# ESP_CAM_VVN_v4.net
KiCad netlist of a schematic drawn in EAGLE
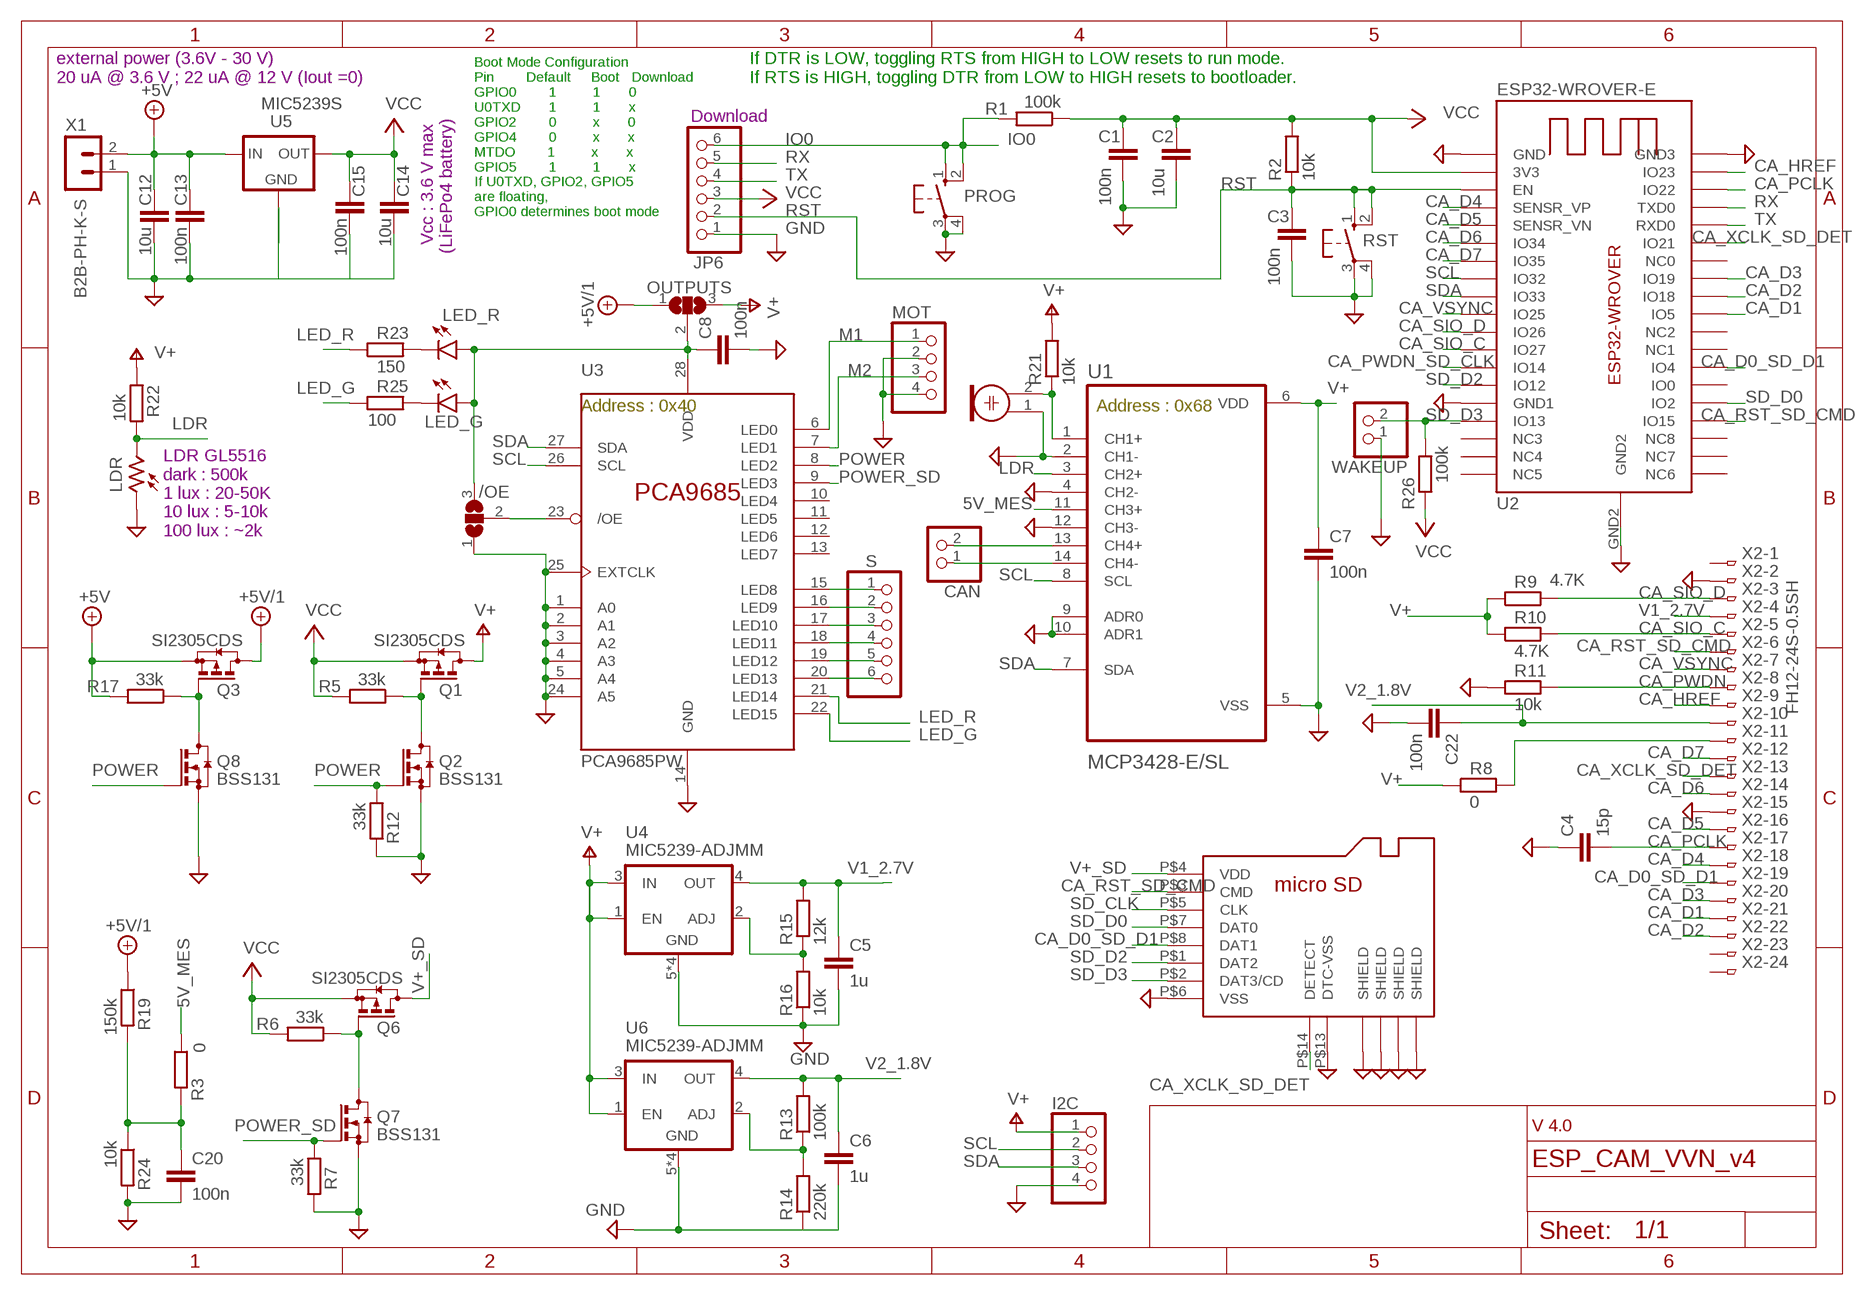
[diagram p0: schematic, sheet 1]

(export (version "E")
  (design (tool "Eeschema 10.0.6"))
  (components
    (comp (ref "/OE")
      (value "SJ2W")
      (footprint "eagle-import:SJ_2")
      (libsource (lib "eagle-import") (part "SJ2W"))
    )
    (comp (ref "C1")
      (value "100n")
      (footprint "eagle-import:C1206")
      (libsource (lib "eagle-import") (part "CC1206"))
    )
    (comp (ref "C2")
      (value "10u")
      (footprint "eagle-import:C1206")
      (libsource (lib "eagle-import") (part "CC1206"))
    )
    (comp (ref "C3")
      (value "100n")
      (footprint "eagle-import:C1206")
      (libsource (lib "eagle-import") (part "CC1206"))
    )
    (comp (ref "C4")
      (value "15p")
      (footprint "eagle-import:C1206")
      (libsource (lib "eagle-import") (part "CC1206"))
    )
    (comp (ref "C5")
      (value "1u")
      (footprint "eagle-import:C1206")
      (libsource (lib "eagle-import") (part "C-EUC1206"))
    )
    (comp (ref "C6")
      (value "1u")
      (footprint "eagle-import:C1206")
      (libsource (lib "eagle-import") (part "C-EUC1206"))
    )
    (comp (ref "C7")
      (value "100n")
      (footprint "eagle-import:C1206")
      (libsource (lib "eagle-import") (part "CC1206"))
    )
    (comp (ref "C8")
      (value "100n")
      (footprint "eagle-import:C1206")
      (libsource (lib "eagle-import") (part "CC1206"))
    )
    (comp (ref "C12")
      (value "10u")
      (footprint "eagle-import:C1206")
      (libsource (lib "eagle-import") (part "CC1206"))
    )
    (comp (ref "C13")
      (value "100n")
      (footprint "eagle-import:C1206")
      (libsource (lib "eagle-import") (part "CC1206"))
    )
    (comp (ref "C14")
      (value "10u")
      (footprint "eagle-import:C1206")
      (libsource (lib "eagle-import") (part "CC1206"))
    )
    (comp (ref "C15")
      (value "100n")
      (footprint "eagle-import:C1206")
      (libsource (lib "eagle-import") (part "CC1206"))
    )
    (comp (ref "C20")
      (value "100n")
      (footprint "eagle-import:C1206")
      (libsource (lib "eagle-import") (part "CC1206"))
    )
    (comp (ref "C22")
      (value "100n")
      (footprint "eagle-import:C1206")
      (libsource (lib "eagle-import") (part "CC1206"))
    )
    (comp (ref "CAN")
      (value "PINHD-1X2")
      (footprint "eagle-import:1X02")
      (libsource (lib "eagle-import") (part "PINHD-1X2"))
    )
    (comp (ref "I2C")
      (value "PINHD-1X4")
      (footprint "eagle-import:1X04")
      (libsource (lib "eagle-import") (part "PINHD-1X4"))
    )
    (comp (ref "JP6")
      (value "PINHD-1X6/90")
      (footprint "eagle-import:1X06_90")
      (libsource (lib "eagle-import") (part "PINHD-1X6/90"))
    )
    (comp (ref "LDR")
      (value "VT93N2")
      (footprint "eagle-import:VT900")
      (libsource (lib "eagle-import") (part "VT93N2"))
    )
    (comp (ref "LED_G")
      (value "LEDSMT1206")
      (footprint "eagle-import:1206")
      (libsource (lib "eagle-import") (part "LEDSMT1206"))
    )
    (comp (ref "LED_R")
      (value "LEDSMT1206")
      (footprint "eagle-import:1206")
      (libsource (lib "eagle-import") (part "LEDSMT1206"))
    )
    (comp (ref "M1")
      (value "ELECTRET_MICROPHON-WM-62PC/62PK")
      (footprint "eagle-import:WM-62PC_62PK")
      (libsource (lib "eagle-import") (part "ELECTRET_MICROPHON-WM-62PC/62PK"))
    )
    (comp (ref "MOT")
      (value "PINHD-1X4")
      (footprint "eagle-import:1X04")
      (libsource (lib "eagle-import") (part "PINHD-1X4"))
    )
    (comp (ref "OUTPUTS")
      (value "SJ2W")
      (footprint "eagle-import:SJ_2")
      (libsource (lib "eagle-import") (part "SJ2W"))
    )
    (comp (ref "PROG")
      (value "10-XX")
      (footprint "eagle-import:B3F-10XX")
      (fields (field (name "MPN") "B3F-1000"))
      (libsource (lib "eagle-import") (part "10-XX"))
    )
    (comp (ref "Q1")
      (value "SI2305CDS")
      (footprint "eagle-import:SOT23")
      (libsource (lib "eagle-import") (part "SI2305CDS"))
    )
    (comp (ref "Q2")
      (value "BSS131")
      (footprint "eagle-import:SOT23")
      (libsource (lib "eagle-import") (part "BSS131"))
    )
    (comp (ref "Q3")
      (value "SI2305CDS")
      (footprint "eagle-import:SOT23")
      (libsource (lib "eagle-import") (part "SI2305CDS"))
    )
    (comp (ref "Q6")
      (value "SI2305CDS")
      (footprint "eagle-import:SOT23")
      (libsource (lib "eagle-import") (part "SI2305CDS"))
    )
    (comp (ref "Q7")
      (value "BSS131")
      (footprint "eagle-import:SOT23")
      (libsource (lib "eagle-import") (part "BSS131"))
    )
    (comp (ref "Q8")
      (value "BSS131")
      (footprint "eagle-import:SOT23")
      (libsource (lib "eagle-import") (part "BSS131"))
    )
    (comp (ref "R1")
      (value "100k")
      (footprint "eagle-import:R1206")
      (libsource (lib "eagle-import") (part "RR1206"))
    )
    (comp (ref "R2")
      (value "10k")
      (footprint "eagle-import:R1206")
      (libsource (lib "eagle-import") (part "RR1206"))
    )
    (comp (ref "R3")
      (value "0")
      (footprint "eagle-import:R1206")
      (libsource (lib "eagle-import") (part "RR1206"))
    )
    (comp (ref "R5")
      (value "33k")
      (footprint "eagle-import:R1206")
      (libsource (lib "eagle-import") (part "RR1206"))
    )
    (comp (ref "R6")
      (value "33k")
      (footprint "eagle-import:R1206")
      (libsource (lib "eagle-import") (part "RR1206"))
    )
    (comp (ref "R7")
      (value "33k")
      (footprint "eagle-import:R1206")
      (libsource (lib "eagle-import") (part "RR1206"))
    )
    (comp (ref "R8")
      (value "0")
      (footprint "eagle-import:R1206")
      (libsource (lib "eagle-import") (part "RR1206"))
    )
    (comp (ref "R9")
      (value "4.7K")
      (footprint "eagle-import:R1206")
      (libsource (lib "eagle-import") (part "RR1206"))
    )
    (comp (ref "R10")
      (value "4.7K")
      (footprint "eagle-import:R1206")
      (libsource (lib "eagle-import") (part "RR1206"))
    )
    (comp (ref "R11")
      (value "10k")
      (footprint "eagle-import:R1206")
      (libsource (lib "eagle-import") (part "RR1206"))
    )
    (comp (ref "R12")
      (value "33k")
      (footprint "eagle-import:R1206")
      (libsource (lib "eagle-import") (part "RR1206"))
    )
    (comp (ref "R13")
      (value "100k")
      (footprint "eagle-import:R1206")
      (libsource (lib "eagle-import") (part "R-EU_R1206"))
    )
    (comp (ref "R14")
      (value "220k")
      (footprint "eagle-import:R1206")
      (libsource (lib "eagle-import") (part "R-EU_R1206"))
    )
    (comp (ref "R15")
      (value "12k")
      (footprint "eagle-import:R1206")
      (libsource (lib "eagle-import") (part "R-EU_R1206"))
    )
    (comp (ref "R16")
      (value "10k")
      (footprint "eagle-import:R1206")
      (libsource (lib "eagle-import") (part "R-EU_R1206"))
    )
    (comp (ref "R17")
      (value "33k")
      (footprint "eagle-import:R1206")
      (libsource (lib "eagle-import") (part "RR1206"))
    )
    (comp (ref "R19")
      (value "150k")
      (footprint "eagle-import:R1206")
      (libsource (lib "eagle-import") (part "RR1206"))
    )
    (comp (ref "R21")
      (value "10k")
      (footprint "eagle-import:R1206")
      (libsource (lib "eagle-import") (part "RR1206"))
    )
    (comp (ref "R22")
      (value "10k")
      (footprint "eagle-import:R1206")
      (libsource (lib "eagle-import") (part "RR1206"))
    )
    (comp (ref "R23")
      (value "150")
      (footprint "eagle-import:R1206")
      (libsource (lib "eagle-import") (part "RR1206"))
    )
    (comp (ref "R24")
      (value "10k")
      (footprint "eagle-import:R1206")
      (libsource (lib "eagle-import") (part "RR1206"))
    )
    (comp (ref "R25")
      (value "100")
      (footprint "eagle-import:R1206")
      (libsource (lib "eagle-import") (part "RR1206"))
    )
    (comp (ref "R26")
      (value "100k")
      (footprint "eagle-import:R1206")
      (libsource (lib "eagle-import") (part "RR1206"))
    )
    (comp (ref "RST")
      (value "10-XX")
      (footprint "eagle-import:B3F-10XX")
      (fields (field (name "MPN") "B3F-1000"))
      (libsource (lib "eagle-import") (part "10-XX"))
    )
    (comp (ref "S")
      (value "PINHD-1X6")
      (footprint "eagle-import:1X06")
      (libsource (lib "eagle-import") (part "PINHD-1X6"))
    )
    (comp (ref "SD1")
      (value "MICRO-SD-8")
      (footprint "eagle-import:MICROSDMOLEX")
      (libsource (lib "eagle-import") (part "MICRO-SD-8"))
    )
    (comp (ref "U1")
      (value "MCP3428-E/SL")
      (footprint "eagle-import:SOIC127P600X175-14N")
      (fields (field (name "MF") "Microchip"))
      (libsource (lib "eagle-import") (part "MCP3428-E/SL"))
    )
    (comp (ref "U2")
      (value "ESP32-WROVER-E")
      (footprint "eagle-import:ESP32-WROVER")
      (libsource (lib "eagle-import") (part "ESP32-WROVER-E"))
    )
    (comp (ref "U3")
      (value "PCA9685PW")
      (footprint "eagle-import:TSSOP28")
      (libsource (lib "eagle-import") (part "PCA9685PW"))
    )
    (comp (ref "U4")
      (value "MIC5239-ADJMM")
      (footprint "eagle-import:MSOP08")
      (libsource (lib "eagle-import") (part "MIC5239-ADJMM"))
    )
    (comp (ref "U5")
      (value "MIC5239S")
      (footprint "eagle-import:SOT223")
      (libsource (lib "eagle-import") (part "MIC5239S"))
    )
    (comp (ref "U6")
      (value "MIC5239-ADJMM")
      (footprint "eagle-import:MSOP08")
      (libsource (lib "eagle-import") (part "MIC5239-ADJMM"))
    )
    (comp (ref "WAKEUP")
      (value "PINHD-1X2")
      (footprint "eagle-import:1X02")
      (libsource (lib "eagle-import") (part "PINHD-1X2"))
    )
    (comp (ref "X1")
      (value "B2B-PH-K-S")
      (footprint "eagle-import:B2B-PH-K-S")
      (libsource (lib "eagle-import") (part "B2B-PH-K-S"))
    )
    (comp (ref "X2")
      (value "FH12-24S-0.5SH")
      (footprint "eagle-import:FH12-24S-0.5SH")
      (fields (field (name "MPN") "FH12-24S-0.5SH(55)"))
      (libsource (lib "eagle-import") (part "FH12-24S-0.5SH"))
    )
  )
  (nets
    (net (code "1") (name "+5V") (class "Default")
      (node (ref "C12") (pin "1") (pinfunction "1_1") (pintype "passive"))
      (node (ref "C13") (pin "1") (pinfunction "1_1") (pintype "passive"))
      (node (ref "Q3") (pin "2") (pinfunction "S_2") (pintype "passive"))
      (node (ref "R17") (pin "2") (pinfunction "2_2") (pintype "passive"))
      (node (ref "U5") (pin "1") (pinfunction "IN_1") (pintype "input"))
      (node (ref "X1") (pin "2") (pinfunction "2_2") (pintype "passive"))
    )
    (net (code "2") (name "+5V{slash}1") (class "Default")
      (node (ref "OUTPUTS") (pin "1") (pinfunction "1_1") (pintype "passive"))
      (node (ref "Q3") (pin "3") (pinfunction "D_3") (pintype "passive"))
      (node (ref "R19") (pin "1") (pinfunction "1_1") (pintype "passive"))
    )
    (net (code "3") (name "/5V_MES") (class "Default")
      (node (ref "R3") (pin "1") (pinfunction "1_1") (pintype "passive"))
      (node (ref "U1") (pin "11") (pinfunction "CH3+_11") (pintype "input"))
    )
    (net (code "4") (name "/CA_D0_SD_D1") (class "Default")
      (node (ref "SD1") (pin "P$8") (pinfunction "DAT1_P$8") (pintype "bidirectional"))
      (node (ref "U2") (pin "IO4") (pinfunction "IO4_IO4") (pintype "bidirectional"))
      (node (ref "X2") (pin "19") (pinfunction "1_19") (pintype "passive"))
    )
    (net (code "5") (name "/CA_D1") (class "Default")
      (node (ref "U2") (pin "IO5") (pinfunction "IO5_IO5") (pintype "bidirectional"))
      (node (ref "X2") (pin "21") (pinfunction "1_21") (pintype "passive"))
    )
    (net (code "6") (name "/CA_D2") (class "Default")
      (node (ref "U2") (pin "IO18") (pinfunction "IO18_IO18") (pintype "bidirectional"))
      (node (ref "X2") (pin "22") (pinfunction "1_22") (pintype "passive"))
    )
    (net (code "7") (name "/CA_D3") (class "Default")
      (node (ref "U2") (pin "IO19") (pinfunction "IO19_IO19") (pintype "bidirectional"))
      (node (ref "X2") (pin "20") (pinfunction "1_20") (pintype "passive"))
    )
    (net (code "8") (name "/CA_D4") (class "Default")
      (node (ref "U2") (pin "SENSOR_VP") (pinfunction "SENSR_VP_SENSOR_VP") (pintype "bidirectional"))
      (node (ref "X2") (pin "18") (pinfunction "1_18") (pintype "passive"))
    )
    (net (code "9") (name "/CA_D5") (class "Default")
      (node (ref "U2") (pin "SENSOR_VN") (pinfunction "SENSR_VN_SENSOR_VN") (pintype "bidirectional"))
      (node (ref "X2") (pin "16") (pinfunction "1_16") (pintype "passive"))
    )
    (net (code "10") (name "/CA_D6") (class "Default")
      (node (ref "U2") (pin "IO34") (pinfunction "IO34_IO34") (pintype "bidirectional"))
      (node (ref "X2") (pin "14") (pinfunction "1_14") (pintype "passive"))
    )
    (net (code "11") (name "/CA_D7") (class "Default")
      (node (ref "U2") (pin "IO35") (pinfunction "IO35_IO35") (pintype "bidirectional"))
      (node (ref "X2") (pin "12") (pinfunction "1_12") (pintype "passive"))
    )
    (net (code "12") (name "/CA_HREF") (class "Default")
      (node (ref "U2") (pin "IO23") (pinfunction "IO23_IO23") (pintype "bidirectional"))
      (node (ref "X2") (pin "9") (pinfunction "1_9") (pintype "passive"))
    )
    (net (code "13") (name "/CA_PCLK") (class "Default")
      (node (ref "C4") (pin "2") (pinfunction "2_2") (pintype "passive"))
      (node (ref "U2") (pin "IO22") (pinfunction "IO22_IO22") (pintype "bidirectional"))
      (node (ref "X2") (pin "17") (pinfunction "1_17") (pintype "passive"))
    )
    (net (code "14") (name "/CA_PWDN") (class "Default")
      (node (ref "R11") (pin "2") (pinfunction "2_2") (pintype "passive"))
      (node (ref "X2") (pin "8") (pinfunction "1_8") (pintype "passive"))
    )
    (net (code "15") (name "/CA_PWDN_SD_CLK") (class "Default")
      (node (ref "U2") (pin "IO14") (pinfunction "IO14_IO14") (pintype "bidirectional"))
    )
    (net (code "16") (name "/CA_RST_SD_CMD") (class "Default")
      (node (ref "SD1") (pin "P$3") (pinfunction "CMD_P$3") (pintype "bidirectional"))
      (node (ref "U2") (pin "IO15") (pinfunction "IO15_IO15") (pintype "bidirectional"))
      (node (ref "X2") (pin "6") (pinfunction "1_6") (pintype "passive"))
    )
    (net (code "17") (name "/CA_SIO_C") (class "Default")
      (node (ref "R10") (pin "2") (pinfunction "2_2") (pintype "passive"))
      (node (ref "U2") (pin "IO27") (pinfunction "IO27_IO27") (pintype "bidirectional"))
      (node (ref "X2") (pin "5") (pinfunction "1_5") (pintype "passive"))
    )
    (net (code "18") (name "/CA_SIO_D") (class "Default")
      (node (ref "R9") (pin "2") (pinfunction "2_2") (pintype "passive"))
      (node (ref "U2") (pin "IO26") (pinfunction "IO26_IO26") (pintype "bidirectional"))
      (node (ref "X2") (pin "3") (pinfunction "1_3") (pintype "passive"))
    )
    (net (code "19") (name "/CA_VSYNC") (class "Default")
      (node (ref "U2") (pin "IO25") (pinfunction "IO25_IO25") (pintype "bidirectional"))
      (node (ref "X2") (pin "7") (pinfunction "1_7") (pintype "passive"))
    )
    (net (code "20") (name "/CA_XCLK_SD_DET") (class "Default")
      (node (ref "SD1") (pin "P$14") (pinfunction "DETECT_P$14") (pintype "power_in"))
      (node (ref "U2") (pin "IO21") (pinfunction "IO21_IO21") (pintype "bidirectional"))
      (node (ref "X2") (pin "13") (pinfunction "1_13") (pintype "passive"))
    )
    (net (code "21") (name "/IO0") (class "Default")
      (node (ref "JP6") (pin "6") (pinfunction "6_6") (pintype "passive"))
      (node (ref "PROG") (pin "1") (pinfunction "S_1") (pintype "passive"))
      (node (ref "PROG") (pin "2") (pinfunction "S1_2") (pintype "passive"))
      (node (ref "R1") (pin "2") (pinfunction "2_2") (pintype "passive"))
    )
    (net (code "22") (name "/LDR") (class "Default")
      (node (ref "LDR") (pin "2") (pinfunction "2_2") (pintype "passive"))
      (node (ref "R22") (pin "2") (pinfunction "2_2") (pintype "passive"))
      (node (ref "U1") (pin "3") (pinfunction "CH2+_3") (pintype "input"))
    )
    (net (code "23") (name "/LED_G") (class "Default")
      (node (ref "R25") (pin "1") (pinfunction "1_1") (pintype "passive"))
      (node (ref "U3") (pin "22") (pinfunction "LED15_22") (pintype "bidirectional"))
    )
    (net (code "24") (name "/LED_R") (class "Default")
      (node (ref "R23") (pin "1") (pinfunction "1_1") (pintype "passive"))
      (node (ref "U3") (pin "21") (pinfunction "LED14_21") (pintype "bidirectional"))
    )
    (net (code "25") (name "/M1") (class "Default")
      (node (ref "MOT") (pin "1") (pinfunction "1_1") (pintype "passive"))
      (node (ref "U3") (pin "6") (pinfunction "LED0_6") (pintype "bidirectional"))
    )
    (net (code "26") (name "/M2") (class "Default")
      (node (ref "MOT") (pin "3") (pinfunction "3_3") (pintype "passive"))
      (node (ref "U3") (pin "7") (pinfunction "LED1_7") (pintype "bidirectional"))
    )
    (net (code "27") (name "/POWER") (class "Default")
      (node (ref "Q2") (pin "1") (pinfunction "G_1") (pintype "passive"))
      (node (ref "Q8") (pin "1") (pinfunction "G_1") (pintype "passive"))
      (node (ref "R12") (pin "1") (pinfunction "1_1") (pintype "passive"))
      (node (ref "U3") (pin "8") (pinfunction "LED2_8") (pintype "bidirectional"))
    )
    (net (code "28") (name "/POWER_SD") (class "Default")
      (node (ref "Q7") (pin "1") (pinfunction "G_1") (pintype "passive"))
      (node (ref "R7") (pin "1") (pinfunction "1_1") (pintype "passive"))
      (node (ref "U3") (pin "9") (pinfunction "LED3_9") (pintype "bidirectional"))
    )
    (net (code "29") (name "/RST") (class "Default")
      (node (ref "C3") (pin "1") (pinfunction "1_1") (pintype "passive"))
      (node (ref "JP6") (pin "2") (pinfunction "2_2") (pintype "passive"))
      (node (ref "R2") (pin "1") (pinfunction "1_1") (pintype "passive"))
      (node (ref "RST") (pin "1") (pinfunction "S_1") (pintype "passive"))
      (node (ref "RST") (pin "2") (pinfunction "S1_2") (pintype "passive"))
      (node (ref "U2") (pin "EN") (pinfunction "EN_EN") (pintype "bidirectional"))
    )
    (net (code "30") (name "/RX") (class "Default")
      (node (ref "JP6") (pin "5") (pinfunction "5_5") (pintype "passive"))
      (node (ref "U2") (pin "TXD0") (pinfunction "TXD0_TXD0") (pintype "bidirectional"))
    )
    (net (code "31") (name "/SCL") (class "Default")
      (node (ref "I2C") (pin "2") (pinfunction "2_2") (pintype "passive"))
      (node (ref "U1") (pin "8") (pinfunction "SCL_8") (pintype "input"))
      (node (ref "U2") (pin "IO32") (pinfunction "IO32_IO32") (pintype "bidirectional"))
      (node (ref "U3") (pin "26") (pinfunction "SCL_26") (pintype "bidirectional"))
    )
    (net (code "32") (name "/SDA") (class "Default")
      (node (ref "I2C") (pin "3") (pinfunction "3_3") (pintype "passive"))
      (node (ref "U1") (pin "7") (pinfunction "SDA_7") (pintype "bidirectional"))
      (node (ref "U2") (pin "IO33") (pinfunction "IO33_IO33") (pintype "bidirectional"))
      (node (ref "U3") (pin "27") (pinfunction "SDA_27") (pintype "bidirectional"))
    )
    (net (code "33") (name "/SD_CLK") (class "Default")
      (node (ref "SD1") (pin "P$5") (pinfunction "CLK_P$5") (pintype "bidirectional"))
    )
    (net (code "34") (name "/SD_D0") (class "Default")
      (node (ref "SD1") (pin "P$7") (pinfunction "DAT0_P$7") (pintype "bidirectional"))
      (node (ref "U2") (pin "IO2") (pinfunction "IO2_IO2") (pintype "bidirectional"))
    )
    (net (code "35") (name "/SD_D2") (class "Default")
      (node (ref "SD1") (pin "P$1") (pinfunction "DAT2_P$1") (pintype "bidirectional"))
      (node (ref "U2") (pin "IO12") (pinfunction "IO12_IO12") (pintype "bidirectional"))
    )
    (net (code "36") (name "/SD_D3") (class "Default")
      (node (ref "R26") (pin "2") (pinfunction "2_2") (pintype "passive"))
      (node (ref "SD1") (pin "P$2") (pinfunction "DAT3/CD_P$2") (pintype "bidirectional"))
      (node (ref "U2") (pin "IO13") (pinfunction "IO13_IO13") (pintype "bidirectional"))
      (node (ref "WAKEUP") (pin "2") (pinfunction "2_2") (pintype "passive"))
    )
    (net (code "37") (name "/TX") (class "Default")
      (node (ref "JP6") (pin "4") (pinfunction "4_4") (pintype "passive"))
      (node (ref "U2") (pin "RXD0") (pinfunction "RXD0_RXD0") (pintype "bidirectional"))
    )
    (net (code "38") (name "/V+_SD") (class "Default")
      (node (ref "Q6") (pin "3") (pinfunction "D_3") (pintype "passive"))
      (node (ref "SD1") (pin "P$4") (pinfunction "VDD_P$4") (pintype "power_in"))
    )
    (net (code "39") (name "/V1_2.7V") (class "Default")
      (node (ref "C5") (pin "1") (pinfunction "1_1") (pintype "passive"))
      (node (ref "R15") (pin "2") (pinfunction "2_2") (pintype "passive"))
      (node (ref "U4") (pin "4") (pinfunction "OUT_4") (pintype "passive"))
      (node (ref "X2") (pin "4") (pinfunction "1_4") (pintype "passive"))
    )
    (net (code "40") (name "/V2_1.8V") (class "Default")
      (node (ref "C22") (pin "1") (pinfunction "1_1") (pintype "passive"))
      (node (ref "C6") (pin "1") (pinfunction "1_1") (pintype "passive"))
      (node (ref "R13") (pin "2") (pinfunction "2_2") (pintype "passive"))
      (node (ref "U6") (pin "4") (pinfunction "OUT_4") (pintype "passive"))
      (node (ref "X2") (pin "10") (pinfunction "1_10") (pintype "passive"))
    )
    (net (code "41") (name "GND") (class "Default")
      (node (ref "/OE") (pin "1") (pinfunction "1_1") (pintype "passive"))
      (node (ref "C1") (pin "2") (pinfunction "2_2") (pintype "passive"))
      (node (ref "C12") (pin "2") (pinfunction "2_2") (pintype "passive"))
      (node (ref "C13") (pin "2") (pinfunction "2_2") (pintype "passive"))
      (node (ref "C14") (pin "2") (pinfunction "2_2") (pintype "passive"))
      (node (ref "C15") (pin "2") (pinfunction "2_2") (pintype "passive"))
      (node (ref "C2") (pin "2") (pinfunction "2_2") (pintype "passive"))
      (node (ref "C20") (pin "2") (pinfunction "2_2") (pintype "passive"))
      (node (ref "C22") (pin "2") (pinfunction "2_2") (pintype "passive"))
      (node (ref "C3") (pin "2") (pinfunction "2_2") (pintype "passive"))
      (node (ref "C4") (pin "1") (pinfunction "1_1") (pintype "passive"))
      (node (ref "C5") (pin "2") (pinfunction "2_2") (pintype "passive"))
      (node (ref "C6") (pin "2") (pinfunction "2_2") (pintype "passive"))
      (node (ref "C7") (pin "2") (pinfunction "2_2") (pintype "passive"))
      (node (ref "C8") (pin "2") (pinfunction "2_2") (pintype "passive"))
      (node (ref "I2C") (pin "4") (pinfunction "4_4") (pintype "passive"))
      (node (ref "JP6") (pin "1") (pinfunction "1_1") (pintype "passive"))
      (node (ref "LDR") (pin "1") (pinfunction "1_1") (pintype "passive"))
      (node (ref "M1") (pin "1") (pinfunction "1_1") (pintype "passive"))
      (node (ref "MOT") (pin "2") (pinfunction "2_2") (pintype "passive"))
      (node (ref "MOT") (pin "4") (pinfunction "4_4") (pintype "passive"))
      (node (ref "PROG") (pin "3") (pinfunction "P_3") (pintype "passive"))
      (node (ref "PROG") (pin "4") (pinfunction "P1_4") (pintype "passive"))
      (node (ref "Q2") (pin "2") (pinfunction "S_2") (pintype "passive"))
      (node (ref "Q7") (pin "2") (pinfunction "S_2") (pintype "passive"))
      (node (ref "Q8") (pin "2") (pinfunction "S_2") (pintype "passive"))
      (node (ref "R11") (pin "1") (pinfunction "1_1") (pintype "passive"))
      (node (ref "R12") (pin "2") (pinfunction "2_2") (pintype "passive"))
      (node (ref "R14") (pin "1") (pinfunction "1_1") (pintype "passive"))
      (node (ref "R16") (pin "1") (pinfunction "1_1") (pintype "passive"))
      (node (ref "R24") (pin "2") (pinfunction "2_2") (pintype "passive"))
      (node (ref "R7") (pin "2") (pinfunction "2_2") (pintype "passive"))
      (node (ref "RST") (pin "3") (pinfunction "P_3") (pintype "passive"))
      (node (ref "RST") (pin "4") (pinfunction "P1_4") (pintype "passive"))
      (node (ref "SD1") (pin "P$10") (pinfunction "SHIELD_P$10") (pintype "power_in"))
      (node (ref "SD1") (pin "P$11") (pinfunction "SHIELD_P$11") (pintype "power_in"))
      (node (ref "SD1") (pin "P$12") (pinfunction "SHIELD_P$12") (pintype "power_in"))
      (node (ref "SD1") (pin "P$13") (pinfunction "DTC-VSS_P$13") (pintype "power_in"))
      (node (ref "SD1") (pin "P$6") (pinfunction "VSS_P$6") (pintype "power_in"))
      (node (ref "SD1") (pin "P$9") (pinfunction "SHIELD_P$9") (pintype "power_in"))
      (node (ref "U1") (pin "10") (pinfunction "ADR1_10") (pintype "bidirectional"))
      (node (ref "U1") (pin "12") (pinfunction "CH3-_12") (pintype "input"))
      (node (ref "U1") (pin "2") (pinfunction "CH1-_2") (pintype "input"))
      (node (ref "U1") (pin "4") (pinfunction "CH2-_4") (pintype "input"))
      (node (ref "U1") (pin "5") (pinfunction "VSS_5") (pintype "power_in"))
      (node (ref "U1") (pin "9") (pinfunction "ADR0_9") (pintype "bidirectional"))
      (node (ref "U2") (pin "GND") (pinfunction "GND_GND") (pintype "bidirectional"))
      (node (ref "U2") (pin "GND1") (pinfunction "GND1_GND1") (pintype "bidirectional"))
      (node (ref "U2") (pin "GND2") (pinfunction "GND2_GND2") (pintype "bidirectional"))
      (node (ref "U2") (pin "GND3") (pinfunction "GND3_GND3") (pintype "bidirectional"))
      (node (ref "U3") (pin "1") (pinfunction "A0_1") (pintype "bidirectional"))
      (node (ref "U3") (pin "14") (pinfunction "GND_14") (pintype "power_in"))
      (node (ref "U3") (pin "2") (pinfunction "A1_2") (pintype "bidirectional"))
      (node (ref "U3") (pin "24") (pinfunction "A5_24") (pintype "bidirectional"))
      (node (ref "U3") (pin "25") (pinfunction "EXTCLK_25") (pintype "input"))
      (node (ref "U3") (pin "3") (pinfunction "A2_3") (pintype "bidirectional"))
      (node (ref "U3") (pin "4") (pinfunction "A3_4") (pintype "bidirectional"))
      (node (ref "U3") (pin "5") (pinfunction "A4_5") (pintype "bidirectional"))
      (node (ref "U4") (pin "5") (pinfunction "GND_5") (pintype "power_in"))
      (node (ref "U4") (pin "6") (pinfunction "GND_6") (pintype "power_in"))
      (node (ref "U4") (pin "7") (pinfunction "GND_7") (pintype "power_in"))
      (node (ref "U4") (pin "8") (pinfunction "GND_8") (pintype "power_in"))
      (node (ref "U5") (pin "2") (pinfunction "GND_2") (pintype "passive"))
      (node (ref "U5") (pin "4") (pinfunction "GND_4") (pintype "passive"))
      (node (ref "U6") (pin "5") (pinfunction "GND_5") (pintype "power_in"))
      (node (ref "U6") (pin "6") (pinfunction "GND_6") (pintype "power_in"))
      (node (ref "U6") (pin "7") (pinfunction "GND_7") (pintype "power_in"))
      (node (ref "U6") (pin "8") (pinfunction "GND_8") (pintype "power_in"))
      (node (ref "WAKEUP") (pin "1") (pinfunction "1_1") (pintype "passive"))
      (node (ref "X1") (pin "1") (pinfunction "1_1") (pintype "passive"))
      (node (ref "X2") (pin "15") (pinfunction "1_15") (pintype "passive"))
      (node (ref "X2") (pin "2") (pinfunction "1_2") (pintype "passive"))
    )
    (net (code "42") (name "Net-(C20-Pad1)") (class "Default")
      (node (ref "C20") (pin "1") (pinfunction "1_1") (pintype "passive"))
      (node (ref "R19") (pin "2") (pinfunction "2_2") (pintype "passive"))
      (node (ref "R24") (pin "1") (pinfunction "1_1") (pintype "passive"))
      (node (ref "R3") (pin "2") (pinfunction "2_2") (pintype "passive"))
    )
    (net (code "43") (name "Net-(LED_G-PadC)") (class "Default")
      (node (ref "LED_G") (pin "C") (pinfunction "C_C") (pintype "passive"))
      (node (ref "R25") (pin "2") (pinfunction "2_2") (pintype "passive"))
    )
    (net (code "44") (name "Net-(LED_R-PadC)") (class "Default")
      (node (ref "LED_R") (pin "C") (pinfunction "C_C") (pintype "passive"))
      (node (ref "R23") (pin "2") (pinfunction "2_2") (pintype "passive"))
    )
    (net (code "45") (name "Net-(Q1-G)") (class "Default")
      (node (ref "Q1") (pin "1") (pinfunction "G_1") (pintype "passive"))
      (node (ref "Q2") (pin "3") (pinfunction "D_3") (pintype "passive"))
      (node (ref "R5") (pin "1") (pinfunction "1_1") (pintype "passive"))
    )
    (net (code "46") (name "Net-(Q3-G)") (class "Default")
      (node (ref "Q3") (pin "1") (pinfunction "G_1") (pintype "passive"))
      (node (ref "Q8") (pin "3") (pinfunction "D_3") (pintype "passive"))
      (node (ref "R17") (pin "1") (pinfunction "1_1") (pintype "passive"))
    )
    (net (code "47") (name "Net-(Q6-G)") (class "Default")
      (node (ref "Q6") (pin "1") (pinfunction "G_1") (pintype "passive"))
      (node (ref "Q7") (pin "3") (pinfunction "D_3") (pintype "passive"))
      (node (ref "R6") (pin "1") (pinfunction "1_1") (pintype "passive"))
    )
    (net (code "48") (name "Net-(U1-CH1+)") (class "Default")
      (node (ref "M1") (pin "2") (pinfunction "2_2") (pintype "passive"))
      (node (ref "R21") (pin "1") (pinfunction "1_1") (pintype "passive"))
      (node (ref "U1") (pin "1") (pinfunction "CH1+_1") (pintype "input"))
    )
    (net (code "49") (name "Net-(U1-CH4+)") (class "Default")
      (node (ref "CAN") (pin "2") (pinfunction "2_2") (pintype "passive"))
      (node (ref "U1") (pin "13") (pinfunction "CH4+_13") (pintype "input"))
    )
    (net (code "50") (name "Net-(U1-CH4-)") (class "Default")
      (node (ref "CAN") (pin "1") (pinfunction "1_1") (pintype "passive"))
      (node (ref "U1") (pin "14") (pinfunction "CH4-_14") (pintype "input"))
    )
    (net (code "51") (name "Net-(U3-LED8)") (class "Default")
      (node (ref "S") (pin "1") (pinfunction "1_1") (pintype "passive"))
      (node (ref "U3") (pin "15") (pinfunction "LED8_15") (pintype "bidirectional"))
    )
    (net (code "52") (name "Net-(U3-LED9)") (class "Default")
      (node (ref "S") (pin "2") (pinfunction "2_2") (pintype "passive"))
      (node (ref "U3") (pin "16") (pinfunction "LED9_16") (pintype "bidirectional"))
    )
    (net (code "53") (name "Net-(U3-LED10)") (class "Default")
      (node (ref "S") (pin "3") (pinfunction "3_3") (pintype "passive"))
      (node (ref "U3") (pin "17") (pinfunction "LED10_17") (pintype "bidirectional"))
    )
    (net (code "54") (name "Net-(U3-LED11)") (class "Default")
      (node (ref "S") (pin "4") (pinfunction "4_4") (pintype "passive"))
      (node (ref "U3") (pin "18") (pinfunction "LED11_18") (pintype "bidirectional"))
    )
    (net (code "55") (name "Net-(U3-LED12)") (class "Default")
      (node (ref "S") (pin "5") (pinfunction "5_5") (pintype "passive"))
      (node (ref "U3") (pin "19") (pinfunction "LED12_19") (pintype "bidirectional"))
    )
    (net (code "56") (name "Net-(U3-LED13)") (class "Default")
      (node (ref "S") (pin "6") (pinfunction "6_6") (pintype "passive"))
      (node (ref "U3") (pin "20") (pinfunction "LED13_20") (pintype "bidirectional"))
    )
    (net (code "57") (name "Net-(U3-VDD)") (class "Default")
      (node (ref "/OE") (pin "3") (pinfunction "3_3") (pintype "passive"))
      (node (ref "C8") (pin "1") (pinfunction "1_1") (pintype "passive"))
      (node (ref "LED_G") (pin "A") (pinfunction "A_A") (pintype "passive"))
      (node (ref "LED_R") (pin "A") (pinfunction "A_A") (pintype "passive"))
      (node (ref "OUTPUTS") (pin "2") (pinfunction "2_2") (pintype "passive"))
      (node (ref "U3") (pin "28") (pinfunction "VDD_28") (pintype "power_in"))
    )
    (net (code "58") (name "Net-(U3-{slash}OE)") (class "Default")
      (node (ref "/OE") (pin "2") (pinfunction "2_2") (pintype "passive"))
      (node (ref "U3") (pin "23") (pinfunction "/OE_23") (pintype "bidirectional"))
    )
    (net (code "59") (name "Net-(U4-ADJ)") (class "Default")
      (node (ref "R15") (pin "1") (pinfunction "1_1") (pintype "passive"))
      (node (ref "R16") (pin "2") (pinfunction "2_2") (pintype "passive"))
      (node (ref "U4") (pin "2") (pinfunction "ADJ_2") (pintype "passive"))
    )
    (net (code "60") (name "Net-(U6-ADJ)") (class "Default")
      (node (ref "R13") (pin "1") (pinfunction "1_1") (pintype "passive"))
      (node (ref "R14") (pin "2") (pinfunction "2_2") (pintype "passive"))
      (node (ref "U6") (pin "2") (pinfunction "ADJ_2") (pintype "passive"))
    )
    (net (code "61") (name "Net-(X2C-1)") (class "Default")
      (node (ref "R8") (pin "2") (pinfunction "2_2") (pintype "passive"))
      (node (ref "X2") (pin "11") (pinfunction "1_11") (pintype "passive"))
    )
    (net (code "62") (name "V+") (class "Default")
      (node (ref "C7") (pin "1") (pinfunction "1_1") (pintype "passive"))
      (node (ref "I2C") (pin "1") (pinfunction "1_1") (pintype "passive"))
      (node (ref "OUTPUTS") (pin "3") (pinfunction "3_3") (pintype "passive"))
      (node (ref "Q1") (pin "3") (pinfunction "D_3") (pintype "passive"))
      (node (ref "R10") (pin "1") (pinfunction "1_1") (pintype "passive"))
      (node (ref "R21") (pin "2") (pinfunction "2_2") (pintype "passive"))
      (node (ref "R22") (pin "1") (pinfunction "1_1") (pintype "passive"))
      (node (ref "R8") (pin "1") (pinfunction "1_1") (pintype "passive"))
      (node (ref "R9") (pin "1") (pinfunction "1_1") (pintype "passive"))
      (node (ref "U1") (pin "6") (pinfunction "VDD_6") (pintype "power_in"))
      (node (ref "U4") (pin "1") (pinfunction "EN_1") (pintype "input"))
      (node (ref "U4") (pin "3") (pinfunction "IN_3") (pintype "input"))
      (node (ref "U6") (pin "1") (pinfunction "EN_1") (pintype "input"))
      (node (ref "U6") (pin "3") (pinfunction "IN_3") (pintype "input"))
    )
    (net (code "63") (name "VCC") (class "Default")
      (node (ref "C1") (pin "1") (pinfunction "1_1") (pintype "passive"))
      (node (ref "C14") (pin "1") (pinfunction "1_1") (pintype "passive"))
      (node (ref "C15") (pin "1") (pinfunction "1_1") (pintype "passive"))
      (node (ref "C2") (pin "1") (pinfunction "1_1") (pintype "passive"))
      (node (ref "JP6") (pin "3") (pinfunction "3_3") (pintype "passive"))
      (node (ref "Q1") (pin "2") (pinfunction "S_2") (pintype "passive"))
      (node (ref "Q6") (pin "2") (pinfunction "S_2") (pintype "passive"))
      (node (ref "R1") (pin "1") (pinfunction "1_1") (pintype "passive"))
      (node (ref "R2") (pin "2") (pinfunction "2_2") (pintype "passive"))
      (node (ref "R26") (pin "1") (pinfunction "1_1") (pintype "passive"))
      (node (ref "R5") (pin "2") (pinfunction "2_2") (pintype "passive"))
      (node (ref "R6") (pin "2") (pinfunction "2_2") (pintype "passive"))
      (node (ref "U2") (pin "VDD33") (pinfunction "3V3_VDD33") (pintype "bidirectional"))
      (node (ref "U5") (pin "3") (pinfunction "OUT_3") (pintype "passive"))
    )
    (net (code "64") (name "unconnected-(U2-NC3-PadCLK)") (class "Default")
      (node (ref "U2") (pin "CLK") (pinfunction "NC3_CLK") (pintype "bidirectional"))
    )
    (net (code "65") (name "unconnected-(U2-NC4-PadCMD)") (class "Default")
      (node (ref "U2") (pin "CMD") (pinfunction "NC4_CMD") (pintype "bidirectional"))
    )
    (net (code "66") (name "unconnected-(U2-NC5-PadSD0)") (class "Default")
      (node (ref "U2") (pin "SD0") (pinfunction "NC5_SD0") (pintype "bidirectional"))
    )
    (net (code "67") (name "unconnected-(U2-NC6-PadSD1)") (class "Default")
      (node (ref "U2") (pin "SD1") (pinfunction "NC6_SD1") (pintype "bidirectional"))
    )
    (net (code "68") (name "unconnected-(U2-NC7-PadSD2)") (class "Default")
      (node (ref "U2") (pin "SD2") (pinfunction "NC7_SD2") (pintype "bidirectional"))
    )
    (net (code "69") (name "unconnected-(U2-NC8-PadSD3)") (class "Default")
      (node (ref "U2") (pin "SD3") (pinfunction "NC8_SD3") (pintype "bidirectional"))
    )
    (net (code "70") (name "unconnected-(U2-PadIO0)") (class "Default")
      (node (ref "U2") (pin "IO0") (pinfunction "IO0_IO0") (pintype "bidirectional"))
    )
    (net (code "71") (name "unconnected-(U2-PadNC0)") (class "Default")
      (node (ref "U2") (pin "NC0") (pinfunction "NC0_NC0") (pintype "bidirectional"))
    )
    (net (code "72") (name "unconnected-(U2-PadNC1)") (class "Default")
      (node (ref "U2") (pin "NC1") (pinfunction "NC1_NC1") (pintype "bidirectional"))
    )
    (net (code "73") (name "unconnected-(U2-PadNC2)") (class "Default")
      (node (ref "U2") (pin "NC2") (pinfunction "NC2_NC2") (pintype "bidirectional"))
    )
    (net (code "74") (name "unconnected-(U3-LED4-Pad10)") (class "Default")
      (node (ref "U3") (pin "10") (pinfunction "LED4_10") (pintype "bidirectional"))
    )
    (net (code "75") (name "unconnected-(U3-LED5-Pad11)") (class "Default")
      (node (ref "U3") (pin "11") (pinfunction "LED5_11") (pintype "bidirectional"))
    )
    (net (code "76") (name "unconnected-(U3-LED6-Pad12)") (class "Default")
      (node (ref "U3") (pin "12") (pinfunction "LED6_12") (pintype "bidirectional"))
    )
    (net (code "77") (name "unconnected-(U3-LED7-Pad13)") (class "Default")
      (node (ref "U3") (pin "13") (pinfunction "LED7_13") (pintype "bidirectional"))
    )
    (net (code "78") (name "unconnected-(X2-Pad1)") (class "Default")
      (node (ref "X2") (pin "1") (pinfunction "1_1") (pintype "passive"))
    )
    (net (code "79") (name "unconnected-(X2P-1-Pad23)") (class "Default")
      (node (ref "X2") (pin "23") (pinfunction "1_23") (pintype "passive"))
    )
    (net (code "80") (name "unconnected-(X2Q-1-Pad24)") (class "Default")
      (node (ref "X2") (pin "24") (pinfunction "1_24") (pintype "passive"))
    )
  )
)
